# 06-Audio.net
KiCad netlist of a schematic drawn in Altium Designer
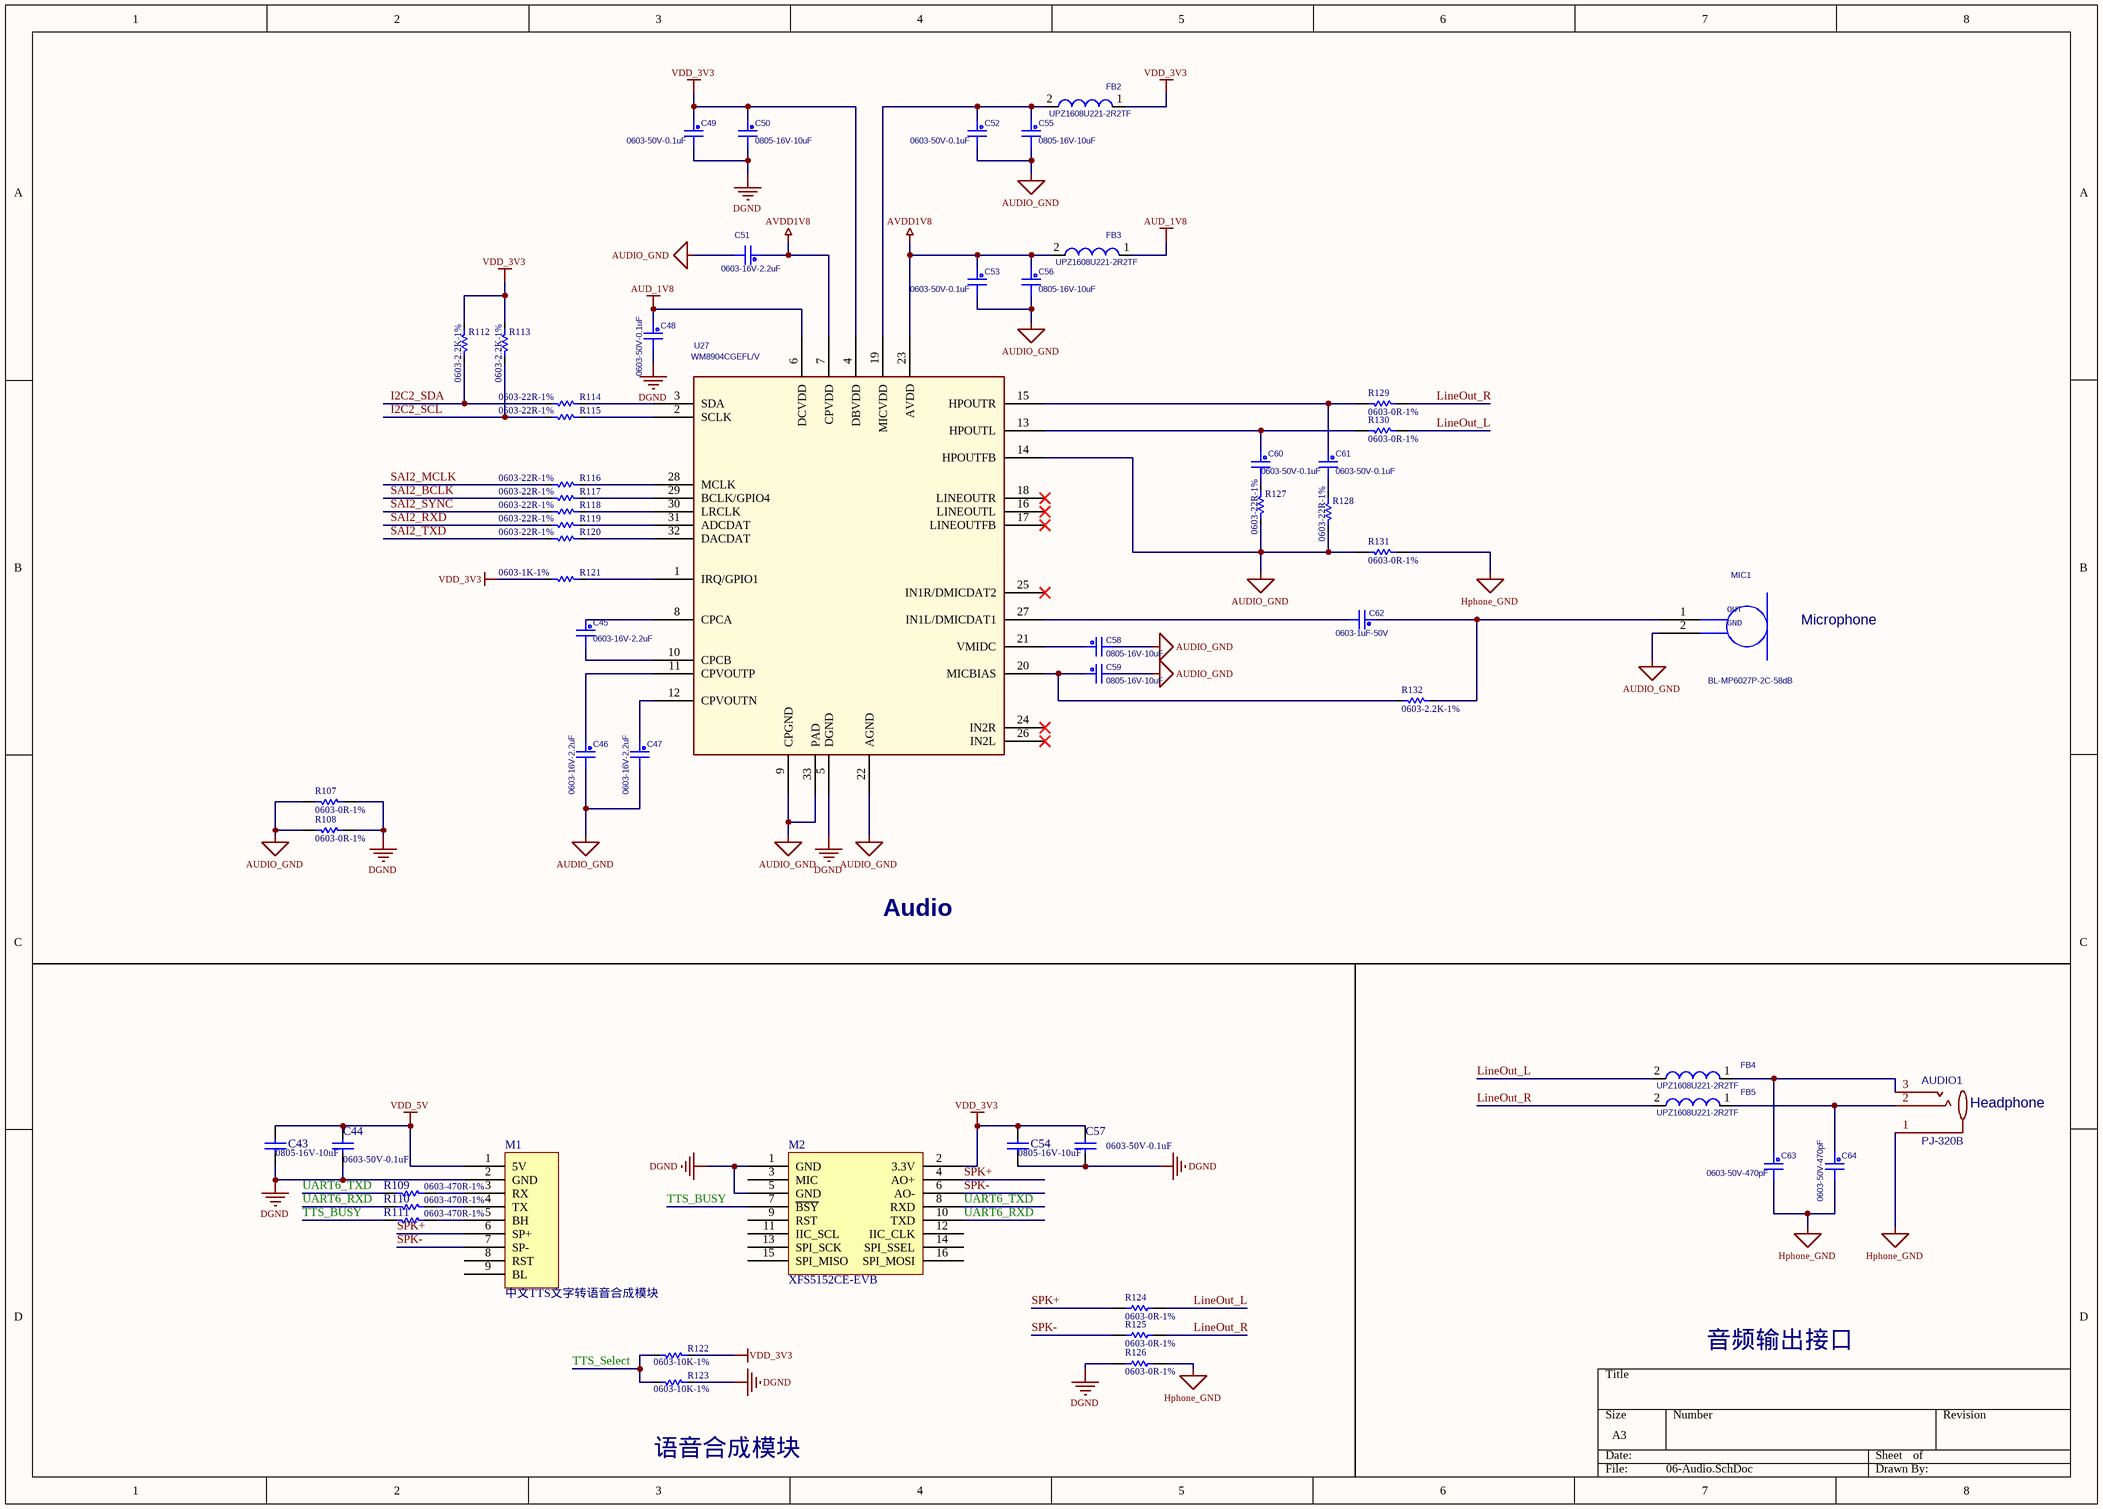
[diagram p0: 06-Audio.SchDoc]

(export (version "E")
  (design (tool "Eeschema 10.0.6"))
  (components
    (comp (ref "AUDIO1")
      (value "PJ-320B")
      (footprint "PJ-320B")
      (fields (field (name "BOM_SUPPLIER PART") "C18594") (field (name "CONTRIBUTOR") "LCSC"))
      (libsource (lib "altium-import") (part "root_2__"))
    )
    (comp (ref "C43")
      (value "0805-16V-10uF")
      (footprint "0805C - 3D")
      (description "Capacitor")
      (fields (field (name "PUBLISHER") "Altium Limited"))
      (libsource (lib "Miscellaneous Devices") (part "Cap"))
    )
    (comp (ref "C44")
      (value "0603-50V-0.1uF")
      (footprint "0603C")
      (description "Capacitor")
      (fields (field (name "PUBLISHER") "Altium Limited"))
      (libsource (lib "Miscellaneous Devices") (part "Cap"))
    )
    (comp (ref "C45")
      (value "0603-16V-2.2uF")
      (footprint "0603C")
      (description "Ceramic Capacitor, +/-10%,X7R,SMD")
      (fields (field (name "MANUFACTURER") "Murata"))
      (libsource (lib "*") (part "CERAMIC CAPACITOR"))
    )
    (comp (ref "C46")
      (value "0603-16V-2.2uF")
      (footprint "0603C")
      (description "Ceramic Capacitor, +/-10%,X7R,SMD")
      (fields (field (name "MANUFACTURER") "Murata"))
      (libsource (lib "*") (part "CERAMIC CAPACITOR"))
    )
    (comp (ref "C47")
      (value "0603-16V-2.2uF")
      (footprint "0603C")
      (description "Ceramic Capacitor, +/-10%,X7R,SMD")
      (fields (field (name "MANUFACTURER") "Murata"))
      (libsource (lib "*") (part "CERAMIC CAPACITOR"))
    )
    (comp (ref "C48")
      (value "0603-50V-0.1uF")
      (footprint "0603C")
      (description "Ceramic Capacitor, +/-10%,X7R,SMD")
      (fields (field (name "MANUFACTURER") "Murata"))
      (libsource (lib "*") (part "CERAMIC CAPACITOR"))
    )
    (comp (ref "C49")
      (value "0603-50V-0.1uF")
      (footprint "0603C")
      (description "Ceramic Capacitor, +/-10%,X7R,SMD")
      (fields (field (name "MANUFACTURER") "Murata"))
      (libsource (lib "*") (part "CERAMIC CAPACITOR"))
    )
    (comp (ref "C50")
      (value "0805-16V-10uF")
      (footprint "0603C")
      (description "Ceramic Capacitor, +/-10%,X7R,SMD")
      (fields (field (name "MANUFACTURER") "Murata"))
      (libsource (lib "*") (part "CERAMIC CAPACITOR"))
    )
    (comp (ref "C51")
      (value "0603-16V-2.2uF")
      (footprint "0603C")
      (description "Ceramic Capacitor, +/-10%,X7R,SMD")
      (fields (field (name "MANUFACTURER") "Murata"))
      (libsource (lib "*") (part "CERAMIC CAPACITOR"))
    )
    (comp (ref "C52")
      (value "0603-50V-0.1uF")
      (footprint "0603C")
      (description "Ceramic Capacitor, +/-10%,X7R,SMD")
      (fields (field (name "MANUFACTURER") "Murata"))
      (libsource (lib "*") (part "CERAMIC CAPACITOR"))
    )
    (comp (ref "C53")
      (value "0603-50V-0.1uF")
      (footprint "0603C")
      (description "Ceramic Capacitor, +/-10%,X7R,SMD")
      (fields (field (name "MANUFACTURER") "Murata"))
      (libsource (lib "*") (part "CERAMIC CAPACITOR"))
    )
    (comp (ref "C54")
      (value "0805-16V-10uF")
      (footprint "0805C - 3D")
      (description "Capacitor")
      (fields (field (name "PUBLISHER") "Altium Limited"))
      (libsource (lib "Miscellaneous Devices") (part "Cap"))
    )
    (comp (ref "C55")
      (value "0805-16V-10uF")
      (footprint "0603C")
      (description "Ceramic Capacitor, +/-10%,X7R,SMD")
      (fields (field (name "MANUFACTURER") "Murata"))
      (libsource (lib "*") (part "CERAMIC CAPACITOR"))
    )
    (comp (ref "C56")
      (value "0805-16V-10uF")
      (footprint "0603C")
      (description "Ceramic Capacitor, +/-10%,X7R,SMD")
      (fields (field (name "MANUFACTURER") "Murata"))
      (libsource (lib "*") (part "CERAMIC CAPACITOR"))
    )
    (comp (ref "C57")
      (value "0603-50V-0.1uF")
      (footprint "0603C")
      (description "Capacitor")
      (fields (field (name "PUBLISHER") "Altium Limited"))
      (libsource (lib "Miscellaneous Devices") (part "Cap"))
    )
    (comp (ref "C58")
      (value "0805-16V-10uF")
      (footprint "0603C")
      (description "Ceramic Capacitor, +/-10%,X7R,SMD")
      (fields (field (name "MANUFACTURER") "Murata"))
      (libsource (lib "*") (part "CERAMIC CAPACITOR"))
    )
    (comp (ref "C59")
      (value "0805-16V-10uF")
      (footprint "0603C")
      (description "Ceramic Capacitor, +/-10%,X7R,SMD")
      (fields (field (name "MANUFACTURER") "Murata"))
      (libsource (lib "*") (part "CERAMIC CAPACITOR"))
    )
    (comp (ref "C60")
      (value "0603-50V-0.1uF")
      (footprint "0603C")
      (description "Ceramic Capacitor, +/-10%,X7R,SMD")
      (fields (field (name "MANUFACTURER") "Murata"))
      (libsource (lib "*") (part "CERAMIC CAPACITOR"))
    )
    (comp (ref "C61")
      (value "0603-50V-0.1uF")
      (footprint "0603C")
      (description "Ceramic Capacitor, +/-10%,X7R,SMD")
      (fields (field (name "MANUFACTURER") "Murata"))
      (libsource (lib "*") (part "CERAMIC CAPACITOR"))
    )
    (comp (ref "C62")
      (value "0603-1uF-50V")
      (footprint "0603C")
      (description "Ceramic Capacitor, +/-10%,X7R,SMD")
      (fields (field (name "MANUFACTURER") "Murata"))
      (libsource (lib "*") (part "CERAMIC CAPACITOR"))
    )
    (comp (ref "C63")
      (value "0603-50V-470pF")
      (footprint "0603C")
      (description "Ceramic Capacitor, +/-10%,X7R,SMD")
      (fields (field (name "MANUFACTURER") "Murata"))
      (libsource (lib "*") (part "CERAMIC CAPACITOR"))
    )
    (comp (ref "C64")
      (value "0603-50V-470pF")
      (footprint "0603C")
      (description "Ceramic Capacitor, +/-10%,X7R,SMD")
      (fields (field (name "MANUFACTURER") "Murata"))
      (libsource (lib "*") (part "CERAMIC CAPACITOR"))
    )
    (comp (ref "FB2")
      (value "UPZ1608U221-2R2TF")
      (footprint "0603L")
      (description "Ferrite Bead,220R@100Mhz, 2000mA,+/-25%,SMD,0603")
      (fields (field (name "MANUFACTURER") "Murata"))
      (libsource (lib "*") (part "Inductor_Dup1"))
    )
    (comp (ref "FB3")
      (value "UPZ1608U221-2R2TF")
      (footprint "VLCF5020T")
      (description "Ferrite Bead,220R@100Mhz, 2000mA,+/-25%,SMD,0805")
      (fields (field (name "MANUFACTURER") "Murata"))
      (libsource (lib "*") (part "Inductor_Dup1"))
    )
    (comp (ref "FB4")
      (value "UPZ1608U221-2R2TF")
      (footprint "0603L")
      (description "Ferrite Bead,220R@100Mhz, 2000mA,+/-25%,SMD,0805")
      (fields (field (name "MANUFACTURER") "Murata"))
      (libsource (lib "*") (part "Inductor_Dup1"))
    )
    (comp (ref "FB5")
      (value "UPZ1608U221-2R2TF")
      (footprint "0603L")
      (description "Ferrite Bead,220R@100Mhz, 2000mA,+/-25%,SMD,0805")
      (fields (field (name "MANUFACTURER") "Murata"))
      (libsource (lib "*") (part "Inductor_Dup1"))
    )
    (comp (ref "M1")
      (value "中文TTS文字转语音合成模块")
      (description "中文TTS文字转语音合成模块,替代SYN6288和XFS5152")
      (libsource (lib "Schlib1") (part "中文TTS文字转语音合成模块"))
    )
    (comp (ref "M2")
      (value "XFS5152CE-EVB")
      (footprint "XFS5152CE_V1.1")
      (description "科大讯飞语音合成模块 XFS5152CE-V1.1")
      (libsource (lib "Schlib1") (part "XFS5152CE-EVB"))
    )
    (comp (ref "MIC1")
      (value "BL-MP6027P-2C-58dB")
      (footprint "MP6027P")
      (description "Microphone Signal to noise ration　≥58　Dimensionφ6.0x2.7")
      (fields (field (name "MANUFACTURER") "HUALIAN"))
      (libsource (lib "*") (part "MIC"))
    )
    (comp (ref "R107")
      (value "0603-0R-1%")
      (footprint "0603R")
      (description "Resistor")
      (fields (field (name "PUBLISHER") "Altium Limited"))
      (libsource (lib "Miscellaneous Devices") (part "Res1"))
    )
    (comp (ref "R108")
      (value "0603-0R-1%")
      (footprint "0603R")
      (description "Resistor")
      (fields (field (name "PUBLISHER") "Altium Limited"))
      (libsource (lib "Miscellaneous Devices") (part "Res1"))
    )
    (comp (ref "R109")
      (value "0603-470R-1%")
      (footprint "0603R")
      (description "Resistor")
      (fields (field (name "PUBLISHER") "Altium Limited"))
      (libsource (lib "Miscellaneous Devices") (part "Res1"))
    )
    (comp (ref "R110")
      (value "0603-470R-1%")
      (footprint "0603R")
      (description "Resistor")
      (fields (field (name "PUBLISHER") "Altium Limited"))
      (libsource (lib "Miscellaneous Devices") (part "Res1"))
    )
    (comp (ref "R111")
      (value "0603-470R-1%")
      (footprint "0603R")
      (description "Resistor")
      (fields (field (name "PUBLISHER") "Altium Limited"))
      (libsource (lib "Miscellaneous Devices") (part "Res1"))
    )
    (comp (ref "R112")
      (value "0603-2.2K-1%")
      (footprint "0603R")
      (description "Resistor")
      (fields (field (name "PUBLISHER") "Altium Limited"))
      (libsource (lib "") (part "Res1_1"))
    )
    (comp (ref "R113")
      (value "0603-2.2K-1%")
      (footprint "0603R")
      (description "Resistor")
      (fields (field (name "PUBLISHER") "Altium Limited"))
      (libsource (lib "") (part "Res1_1"))
    )
    (comp (ref "R114")
      (value "0603-22R-1%")
      (footprint "0603R")
      (description "Resistor")
      (fields (field (name "PUBLISHER") "Altium Limited"))
      (libsource (lib "") (part "Res1_1"))
    )
    (comp (ref "R115")
      (value "0603-22R-1%")
      (footprint "0603R")
      (description "Resistor")
      (fields (field (name "PUBLISHER") "Altium Limited"))
      (libsource (lib "") (part "Res1_1"))
    )
    (comp (ref "R116")
      (value "0603-22R-1%")
      (footprint "0603R")
      (description "Resistor")
      (fields (field (name "PUBLISHER") "Altium Limited"))
      (libsource (lib "") (part "Res1_1"))
    )
    (comp (ref "R117")
      (value "0603-22R-1%")
      (footprint "0603R")
      (description "Resistor")
      (fields (field (name "PUBLISHER") "Altium Limited"))
      (libsource (lib "") (part "Res1_1"))
    )
    (comp (ref "R118")
      (value "0603-22R-1%")
      (footprint "0603R")
      (description "Resistor")
      (fields (field (name "PUBLISHER") "Altium Limited"))
      (libsource (lib "") (part "Res1_1"))
    )
    (comp (ref "R119")
      (value "0603-22R-1%")
      (footprint "0603R")
      (description "Resistor")
      (fields (field (name "PUBLISHER") "Altium Limited"))
      (libsource (lib "") (part "Res1_1"))
    )
    (comp (ref "R120")
      (value "0603-22R-1%")
      (footprint "0603R")
      (description "Resistor")
      (fields (field (name "PUBLISHER") "Altium Limited"))
      (libsource (lib "") (part "Res1_1"))
    )
    (comp (ref "R121")
      (value "0603-1K-1%")
      (footprint "0603R")
      (description "Resistor")
      (fields (field (name "PUBLISHER") "Altium Limited"))
      (libsource (lib "") (part "Res1_1"))
    )
    (comp (ref "R122")
      (value "0603-10K-1%")
      (footprint "0603R")
      (description "Resistor")
      (fields (field (name "PUBLISHER") "Altium Limited"))
      (libsource (lib "") (part "Res1_1"))
    )
    (comp (ref "R123")
      (value "0603-10K-1%")
      (footprint "0603R")
      (description "Resistor")
      (fields (field (name "PUBLISHER") "Altium Limited"))
      (libsource (lib "") (part "Res1_1"))
    )
    (comp (ref "R124")
      (value "0603-0R-1%")
      (footprint "0603R")
      (description "Resistor")
      (fields (field (name "PUBLISHER") "Altium Limited"))
      (libsource (lib "Miscellaneous Devices") (part "Res1"))
    )
    (comp (ref "R125")
      (value "0603-0R-1%")
      (footprint "0603R")
      (description "Resistor")
      (fields (field (name "PUBLISHER") "Altium Limited"))
      (libsource (lib "Miscellaneous Devices") (part "Res1"))
    )
    (comp (ref "R126")
      (value "0603-0R-1%")
      (footprint "0603R")
      (description "Resistor")
      (fields (field (name "PUBLISHER") "Altium Limited"))
      (libsource (lib "Miscellaneous Devices") (part "Res1"))
    )
    (comp (ref "R127")
      (value "0603-22R-1%")
      (footprint "0603R")
      (description "Resistor")
      (fields (field (name "PUBLISHER") "Altium Limited"))
      (libsource (lib "") (part "Res1_1"))
    )
    (comp (ref "R128")
      (value "0603-22R-1%")
      (footprint "0603R")
      (description "Resistor")
      (fields (field (name "PUBLISHER") "Altium Limited"))
      (libsource (lib "") (part "Res1_1"))
    )
    (comp (ref "R129")
      (value "0603-0R-1%")
      (footprint "0603R")
      (description "Resistor")
      (fields (field (name "PUBLISHER") "Altium Limited"))
      (libsource (lib "Miscellaneous Devices") (part "Res1"))
    )
    (comp (ref "R130")
      (value "0603-0R-1%")
      (footprint "0603R")
      (description "Resistor")
      (fields (field (name "PUBLISHER") "Altium Limited"))
      (libsource (lib "Miscellaneous Devices") (part "Res1"))
    )
    (comp (ref "R131")
      (value "0603-0R-1%")
      (footprint "0603R")
      (description "Resistor")
      (fields (field (name "PUBLISHER") "Altium Limited"))
      (libsource (lib "Miscellaneous Devices") (part "Res1"))
    )
    (comp (ref "R132")
      (value "0603-2.2K-1%")
      (footprint "0603R")
      (description "Resistor")
      (fields (field (name "PUBLISHER") "Altium Limited"))
      (libsource (lib "") (part "Res1_1"))
    )
    (comp (ref "U27")
      (value "WM8904CGEFL/V")
      (footprint "qfn32-0_4")
      (description "IC,Ultra Low Power CODEC for Portable Audio Applications,SMD,QFN-32")
      (fields (field (name "MANUFACTURER") "Wolfson"))
      (libsource (lib "*") (part "WM8904"))
    )
  )
  (nets
    (net (code "1") (name "/I2C2_SCL") (class "Default")
      (node (ref "R113") (pin "1") (pinfunction "1_1") (pintype "passive"))
      (node (ref "R115") (pin "1") (pinfunction "1_1") (pintype "passive"))
    )
    (net (code "2") (name "/I2C2_SDA") (class "Default")
      (node (ref "R112") (pin "1") (pinfunction "1_1") (pintype "passive"))
      (node (ref "R114") (pin "1") (pinfunction "1_1") (pintype "passive"))
    )
    (net (code "3") (name "/LineOut_L") (class "Default")
      (node (ref "FB4") (pin "2") (pinfunction "2_2") (pintype "passive"))
      (node (ref "R124") (pin "1") (pinfunction "1_1") (pintype "passive"))
      (node (ref "R130") (pin "2") (pinfunction "2_2") (pintype "passive"))
    )
    (net (code "4") (name "/LineOut_R") (class "Default")
      (node (ref "FB5") (pin "2") (pinfunction "2_2") (pintype "passive"))
      (node (ref "R125") (pin "1") (pinfunction "1_1") (pintype "passive"))
      (node (ref "R129") (pin "2") (pinfunction "2_2") (pintype "passive"))
    )
    (net (code "5") (name "/SAI2_BCLK") (class "Default")
      (node (ref "R117") (pin "1") (pinfunction "1_1") (pintype "passive"))
    )
    (net (code "6") (name "/SAI2_MCLK") (class "Default")
      (node (ref "R116") (pin "1") (pinfunction "1_1") (pintype "passive"))
    )
    (net (code "7") (name "/SAI2_RXD") (class "Default")
      (node (ref "R119") (pin "1") (pinfunction "1_1") (pintype "passive"))
    )
    (net (code "8") (name "/SAI2_SYNC") (class "Default")
      (node (ref "R118") (pin "1") (pinfunction "1_1") (pintype "passive"))
    )
    (net (code "9") (name "/SAI2_TXD") (class "Default")
      (node (ref "R120") (pin "1") (pinfunction "1_1") (pintype "passive"))
    )
    (net (code "10") (name "/SPK+") (class "Default")
      (node (ref "M1") (pin "6") (pinfunction "SP+_6") (pintype "passive"))
      (node (ref "M2") (pin "4") (pinfunction "AO+_4") (pintype "passive"))
      (node (ref "R124") (pin "2") (pinfunction "2_2") (pintype "passive"))
    )
    (net (code "11") (name "/SPK-") (class "Default")
      (node (ref "M1") (pin "7") (pinfunction "SP-_7") (pintype "passive"))
      (node (ref "M2") (pin "6") (pinfunction "AO-_6") (pintype "passive"))
      (node (ref "R125") (pin "2") (pinfunction "2_2") (pintype "passive"))
    )
    (net (code "12") (name "/TTS_BUSY") (class "Default")
      (node (ref "M2") (pin "7") (pinfunction "~{BSY}_7") (pintype "passive"))
      (node (ref "R111") (pin "2") (pinfunction "2_2") (pintype "passive"))
    )
    (net (code "13") (name "/TTS_Select") (class "Default")
      (node (ref "R122") (pin "1") (pinfunction "1_1") (pintype "passive"))
      (node (ref "R123") (pin "1") (pinfunction "1_1") (pintype "passive"))
    )
    (net (code "14") (name "/UART6_RXD") (class "Default")
      (node (ref "M2") (pin "10") (pinfunction "TXD_10") (pintype "passive"))
      (node (ref "R110") (pin "2") (pinfunction "2_2") (pintype "passive"))
    )
    (net (code "15") (name "/UART6_TXD") (class "Default")
      (node (ref "M2") (pin "8") (pinfunction "RXD_8") (pintype "passive"))
      (node (ref "R109") (pin "2") (pinfunction "2_2") (pintype "passive"))
    )
    (net (code "16") (name "AUDIO_GND") (class "Default")
      (node (ref "C46") (pin "2") (pinfunction "2_2") (pintype "passive"))
      (node (ref "C47") (pin "2") (pinfunction "2_2") (pintype "passive"))
      (node (ref "C51") (pin "2") (pinfunction "2_2") (pintype "passive"))
      (node (ref "C52") (pin "2") (pinfunction "2_2") (pintype "passive"))
      (node (ref "C53") (pin "2") (pinfunction "2_2") (pintype "passive"))
      (node (ref "C55") (pin "2") (pinfunction "2_2") (pintype "passive"))
      (node (ref "C56") (pin "2") (pinfunction "2_2") (pintype "passive"))
      (node (ref "C58") (pin "2") (pinfunction "2_2") (pintype "passive"))
      (node (ref "C59") (pin "2") (pinfunction "2_2") (pintype "passive"))
      (node (ref "MIC1") (pin "2") (pinfunction "GND_2") (pintype "passive"))
      (node (ref "R107") (pin "1") (pinfunction "1_1") (pintype "passive"))
      (node (ref "R108") (pin "1") (pinfunction "1_1") (pintype "passive"))
      (node (ref "R127") (pin "1") (pinfunction "1_1") (pintype "passive"))
      (node (ref "R128") (pin "1") (pinfunction "1_1") (pintype "passive"))
      (node (ref "R131") (pin "1") (pinfunction "1_1") (pintype "passive"))
      (node (ref "U27") (pin "14") (pinfunction "HPOUTFB_14") (pintype "passive"))
      (node (ref "U27") (pin "22") (pinfunction "AGND_22") (pintype "passive"))
      (node (ref "U27") (pin "33") (pinfunction "PAD_33") (pintype "passive"))
      (node (ref "U27") (pin "9") (pinfunction "CPGND_9") (pintype "passive"))
    )
    (net (code "17") (name "AUD_1V8") (class "Default")
      (node (ref "C48") (pin "1") (pinfunction "1_1") (pintype "passive"))
      (node (ref "FB3") (pin "1") (pinfunction "1_1") (pintype "passive"))
      (node (ref "U27") (pin "6") (pinfunction "DCVDD_6") (pintype "passive"))
    )
    (net (code "18") (name "AVDD1V8") (class "Default")
      (node (ref "C51") (pin "1") (pinfunction "1_1") (pintype "passive"))
      (node (ref "C53") (pin "1") (pinfunction "1_1") (pintype "passive"))
      (node (ref "C56") (pin "1") (pinfunction "1_1") (pintype "passive"))
      (node (ref "FB3") (pin "2") (pinfunction "2_2") (pintype "passive"))
      (node (ref "U27") (pin "23") (pinfunction "AVDD_23") (pintype "passive"))
      (node (ref "U27") (pin "7") (pinfunction "CPVDD_7") (pintype "passive"))
    )
    (net (code "19") (name "DGND") (class "Default")
      (node (ref "C43") (pin "2") (pinfunction "2_2") (pintype "passive"))
      (node (ref "C44") (pin "2") (pinfunction "2_2") (pintype "passive"))
      (node (ref "C48") (pin "2") (pinfunction "2_2") (pintype "passive"))
      (node (ref "C49") (pin "2") (pinfunction "2_2") (pintype "passive"))
      (node (ref "C50") (pin "2") (pinfunction "2_2") (pintype "passive"))
      (node (ref "C54") (pin "2") (pinfunction "2_2") (pintype "passive"))
      (node (ref "C57") (pin "2") (pinfunction "2_2") (pintype "passive"))
      (node (ref "M1") (pin "2") (pinfunction "GND_2") (pintype "passive"))
      (node (ref "M2") (pin "1") (pinfunction "GND_1") (pintype "passive"))
      (node (ref "M2") (pin "5") (pinfunction "GND_5") (pintype "passive"))
      (node (ref "R107") (pin "2") (pinfunction "2_2") (pintype "passive"))
      (node (ref "R108") (pin "2") (pinfunction "2_2") (pintype "passive"))
      (node (ref "R123") (pin "2") (pinfunction "2_2") (pintype "passive"))
      (node (ref "R126") (pin "2") (pinfunction "2_2") (pintype "passive"))
      (node (ref "U27") (pin "5") (pinfunction "DGND_5") (pintype "passive"))
    )
    (net (code "20") (name "Hphone_GND") (class "Default")
      (node (ref "AUDIO1") (pin "1") (pinfunction "1_1") (pintype "passive"))
      (node (ref "C63") (pin "2") (pinfunction "2_2") (pintype "passive"))
      (node (ref "C64") (pin "2") (pinfunction "2_2") (pintype "passive"))
      (node (ref "R126") (pin "1") (pinfunction "1_1") (pintype "passive"))
      (node (ref "R131") (pin "2") (pinfunction "2_2") (pintype "passive"))
    )
    (net (code "21") (name "Net-(AUDIO1-Pad2)") (class "Default")
      (node (ref "AUDIO1") (pin "2") (pinfunction "2_2") (pintype "passive"))
      (node (ref "C64") (pin "1") (pinfunction "1_1") (pintype "passive"))
      (node (ref "FB5") (pin "1") (pinfunction "1_1") (pintype "passive"))
    )
    (net (code "22") (name "Net-(AUDIO1-Pad3)") (class "Default")
      (node (ref "AUDIO1") (pin "3") (pinfunction "3_3") (pintype "passive"))
      (node (ref "C63") (pin "1") (pinfunction "1_1") (pintype "passive"))
      (node (ref "FB4") (pin "1") (pinfunction "1_1") (pintype "passive"))
    )
    (net (code "23") (name "Net-(C60-Pad2)") (class "Default")
      (node (ref "C60") (pin "2") (pinfunction "2_2") (pintype "passive"))
      (node (ref "R127") (pin "2") (pinfunction "2_2") (pintype "passive"))
    )
    (net (code "24") (name "Net-(C61-Pad2)") (class "Default")
      (node (ref "C61") (pin "2") (pinfunction "2_2") (pintype "passive"))
      (node (ref "R128") (pin "2") (pinfunction "2_2") (pintype "passive"))
    )
    (net (code "25") (name "Net-(M1-BH)") (class "Default")
      (node (ref "M1") (pin "5") (pinfunction "BH_5") (pintype "passive"))
      (node (ref "R111") (pin "1") (pinfunction "1_1") (pintype "passive"))
    )
    (net (code "26") (name "Net-(M1-RX)") (class "Default")
      (node (ref "M1") (pin "3") (pinfunction "RX_3") (pintype "passive"))
      (node (ref "R109") (pin "1") (pinfunction "1_1") (pintype "passive"))
    )
    (net (code "27") (name "Net-(M1-TX)") (class "Default")
      (node (ref "M1") (pin "4") (pinfunction "TX_4") (pintype "passive"))
      (node (ref "R110") (pin "1") (pinfunction "1_1") (pintype "passive"))
    )
    (net (code "28") (name "Net-(MIC1-OUTPUT)") (class "Default")
      (node (ref "C62") (pin "1") (pinfunction "1_1") (pintype "passive"))
      (node (ref "MIC1") (pin "1") (pinfunction "OUTPUT_1") (pintype "passive"))
      (node (ref "R132") (pin "1") (pinfunction "1_1") (pintype "passive"))
    )
    (net (code "29") (name "Net-(U27-ADCDAT)") (class "Default")
      (node (ref "R119") (pin "2") (pinfunction "2_2") (pintype "passive"))
      (node (ref "U27") (pin "31") (pinfunction "ADCDAT_31") (pintype "passive"))
    )
    (net (code "30") (name "Net-(U27-BCLK{slash}GPIO4)") (class "Default")
      (node (ref "R117") (pin "2") (pinfunction "2_2") (pintype "passive"))
      (node (ref "U27") (pin "29") (pinfunction "BCLK/GPIO4_29") (pintype "passive"))
    )
    (net (code "31") (name "Net-(U27-CPCA)") (class "Default")
      (node (ref "C45") (pin "1") (pinfunction "1_1") (pintype "passive"))
      (node (ref "U27") (pin "8") (pinfunction "CPCA_8") (pintype "passive"))
    )
    (net (code "32") (name "Net-(U27-CPCB)") (class "Default")
      (node (ref "C45") (pin "2") (pinfunction "2_2") (pintype "passive"))
      (node (ref "U27") (pin "10") (pinfunction "CPCB_10") (pintype "passive"))
    )
    (net (code "33") (name "Net-(U27-CPVOUTN)") (class "Default")
      (node (ref "C47") (pin "1") (pinfunction "1_1") (pintype "passive"))
      (node (ref "U27") (pin "12") (pinfunction "CPVOUTN_12") (pintype "passive"))
    )
    (net (code "34") (name "Net-(U27-CPVOUTP)") (class "Default")
      (node (ref "C46") (pin "1") (pinfunction "1_1") (pintype "passive"))
      (node (ref "U27") (pin "11") (pinfunction "CPVOUTP_11") (pintype "passive"))
    )
    (net (code "35") (name "Net-(U27-DACDAT)") (class "Default")
      (node (ref "R120") (pin "2") (pinfunction "2_2") (pintype "passive"))
      (node (ref "U27") (pin "32") (pinfunction "DACDAT_32") (pintype "passive"))
    )
    (net (code "36") (name "Net-(U27-HPOUTL)") (class "Default")
      (node (ref "C60") (pin "1") (pinfunction "1_1") (pintype "passive"))
      (node (ref "R130") (pin "1") (pinfunction "1_1") (pintype "passive"))
      (node (ref "U27") (pin "13") (pinfunction "HPOUTL_13") (pintype "passive"))
    )
    (net (code "37") (name "Net-(U27-HPOUTR)") (class "Default")
      (node (ref "C61") (pin "1") (pinfunction "1_1") (pintype "passive"))
      (node (ref "R129") (pin "1") (pinfunction "1_1") (pintype "passive"))
      (node (ref "U27") (pin "15") (pinfunction "HPOUTR_15") (pintype "passive"))
    )
    (net (code "38") (name "Net-(U27-IN1L{slash}DMICDAT1)") (class "Default")
      (node (ref "C62") (pin "2") (pinfunction "2_2") (pintype "passive"))
      (node (ref "U27") (pin "27") (pinfunction "IN1L/DMICDAT1_27") (pintype "passive"))
    )
    (net (code "39") (name "Net-(U27-IRQ{slash}GPIO1)") (class "Default")
      (node (ref "R121") (pin "2") (pinfunction "2_2") (pintype "passive"))
      (node (ref "U27") (pin "1") (pinfunction "IRQ/GPIO1_1") (pintype "passive"))
    )
    (net (code "40") (name "Net-(U27-LRCLK)") (class "Default")
      (node (ref "R118") (pin "2") (pinfunction "2_2") (pintype "passive"))
      (node (ref "U27") (pin "30") (pinfunction "LRCLK_30") (pintype "passive"))
    )
    (net (code "41") (name "Net-(U27-MCLK)") (class "Default")
      (node (ref "R116") (pin "2") (pinfunction "2_2") (pintype "passive"))
      (node (ref "U27") (pin "28") (pinfunction "MCLK_28") (pintype "passive"))
    )
    (net (code "42") (name "Net-(U27-MICBIAS)") (class "Default")
      (node (ref "C59") (pin "1") (pinfunction "1_1") (pintype "passive"))
      (node (ref "R132") (pin "2") (pinfunction "2_2") (pintype "passive"))
      (node (ref "U27") (pin "20") (pinfunction "MICBIAS_20") (pintype "passive"))
    )
    (net (code "43") (name "Net-(U27-MICVDD)") (class "Default")
      (node (ref "C52") (pin "1") (pinfunction "1_1") (pintype "passive"))
      (node (ref "C55") (pin "1") (pinfunction "1_1") (pintype "passive"))
      (node (ref "FB2") (pin "2") (pinfunction "2_2") (pintype "passive"))
      (node (ref "U27") (pin "19") (pinfunction "MICVDD_19") (pintype "passive"))
    )
    (net (code "44") (name "Net-(U27-SCLK)") (class "Default")
      (node (ref "R115") (pin "2") (pinfunction "2_2") (pintype "passive"))
      (node (ref "U27") (pin "2") (pinfunction "SCLK_2") (pintype "passive"))
    )
    (net (code "45") (name "Net-(U27-SDA)") (class "Default")
      (node (ref "R114") (pin "2") (pinfunction "2_2") (pintype "passive"))
      (node (ref "U27") (pin "3") (pinfunction "SDA_3") (pintype "passive"))
    )
    (net (code "46") (name "Net-(U27-VMIDC)") (class "Default")
      (node (ref "C58") (pin "1") (pinfunction "1_1") (pintype "passive"))
      (node (ref "U27") (pin "21") (pinfunction "VMIDC_21") (pintype "passive"))
    )
    (net (code "47") (name "VDD_3V3") (class "Default")
      (node (ref "C49") (pin "1") (pinfunction "1_1") (pintype "passive"))
      (node (ref "C50") (pin "1") (pinfunction "1_1") (pintype "passive"))
      (node (ref "C54") (pin "1") (pinfunction "1_1") (pintype "passive"))
      (node (ref "C57") (pin "1") (pinfunction "1_1") (pintype "passive"))
      (node (ref "FB2") (pin "1") (pinfunction "1_1") (pintype "passive"))
      (node (ref "M2") (pin "2") (pinfunction "3.3V_2") (pintype "passive"))
      (node (ref "R112") (pin "2") (pinfunction "2_2") (pintype "passive"))
      (node (ref "R113") (pin "2") (pinfunction "2_2") (pintype "passive"))
      (node (ref "R121") (pin "1") (pinfunction "1_1") (pintype "passive"))
      (node (ref "R122") (pin "2") (pinfunction "2_2") (pintype "passive"))
      (node (ref "U27") (pin "4") (pinfunction "DBVDD_4") (pintype "passive"))
    )
    (net (code "48") (name "VDD_5V") (class "Default")
      (node (ref "C43") (pin "1") (pinfunction "1_1") (pintype "passive"))
      (node (ref "C44") (pin "1") (pinfunction "1_1") (pintype "passive"))
      (node (ref "M1") (pin "1") (pinfunction "5V_1") (pintype "passive"))
    )
    (net (code "49") (name "unconnected-(M1-BL-Pad9)") (class "Default")
      (node (ref "M1") (pin "9") (pinfunction "BL_9") (pintype "passive"))
    )
    (net (code "50") (name "unconnected-(M1-RST-Pad8)") (class "Default")
      (node (ref "M1") (pin "8") (pinfunction "RST_8") (pintype "passive"))
    )
    (net (code "51") (name "unconnected-(M2-IIC_CLK-Pad12)") (class "Default")
      (node (ref "M2") (pin "12") (pinfunction "IIC_CLK_12") (pintype "passive"))
    )
    (net (code "52") (name "unconnected-(M2-IIC_SCL-Pad11)") (class "Default")
      (node (ref "M2") (pin "11") (pinfunction "IIC_SCL_11") (pintype "passive"))
    )
    (net (code "53") (name "unconnected-(M2-MIC-Pad3)") (class "Default")
      (node (ref "M2") (pin "3") (pinfunction "MIC_3") (pintype "passive"))
    )
    (net (code "54") (name "unconnected-(M2-RST-Pad9)") (class "Default")
      (node (ref "M2") (pin "9") (pinfunction "RST_9") (pintype "passive"))
    )
    (net (code "55") (name "unconnected-(M2-SPI_MISO-Pad15)") (class "Default")
      (node (ref "M2") (pin "15") (pinfunction "SPI_MISO_15") (pintype "passive"))
    )
    (net (code "56") (name "unconnected-(M2-SPI_MOSI-Pad16)") (class "Default")
      (node (ref "M2") (pin "16") (pinfunction "SPI_MOSI_16") (pintype "passive"))
    )
    (net (code "57") (name "unconnected-(M2-SPI_SCK-Pad13)") (class "Default")
      (node (ref "M2") (pin "13") (pinfunction "SPI_SCK_13") (pintype "passive"))
    )
    (net (code "58") (name "unconnected-(M2-SPI_SSEL-Pad14)") (class "Default")
      (node (ref "M2") (pin "14") (pinfunction "SPI_SSEL_14") (pintype "passive"))
    )
    (net (code "59") (name "unconnected-(U27-IN1R{slash}DMICDAT2-Pad25)") (class "Default")
      (node (ref "U27") (pin "25") (pinfunction "IN1R/DMICDAT2_25") (pintype "passive+no_connect"))
    )
    (net (code "60") (name "unconnected-(U27-IN2L-Pad26)") (class "Default")
      (node (ref "U27") (pin "26") (pinfunction "IN2L_26") (pintype "passive+no_connect"))
    )
    (net (code "61") (name "unconnected-(U27-IN2R-Pad24)") (class "Default")
      (node (ref "U27") (pin "24") (pinfunction "IN2R_24") (pintype "passive+no_connect"))
    )
    (net (code "62") (name "unconnected-(U27-LINEOUTFB-Pad17)") (class "Default")
      (node (ref "U27") (pin "17") (pinfunction "LINEOUTFB_17") (pintype "passive+no_connect"))
    )
    (net (code "63") (name "unconnected-(U27-LINEOUTL-Pad16)") (class "Default")
      (node (ref "U27") (pin "16") (pinfunction "LINEOUTL_16") (pintype "passive+no_connect"))
    )
    (net (code "64") (name "unconnected-(U27-LINEOUTR-Pad18)") (class "Default")
      (node (ref "U27") (pin "18") (pinfunction "LINEOUTR_18") (pintype "passive+no_connect"))
    )
  )
)
